# C64_Keyb-Test-ext.net
KiCad netlist of a schematic drawn in EAGLE
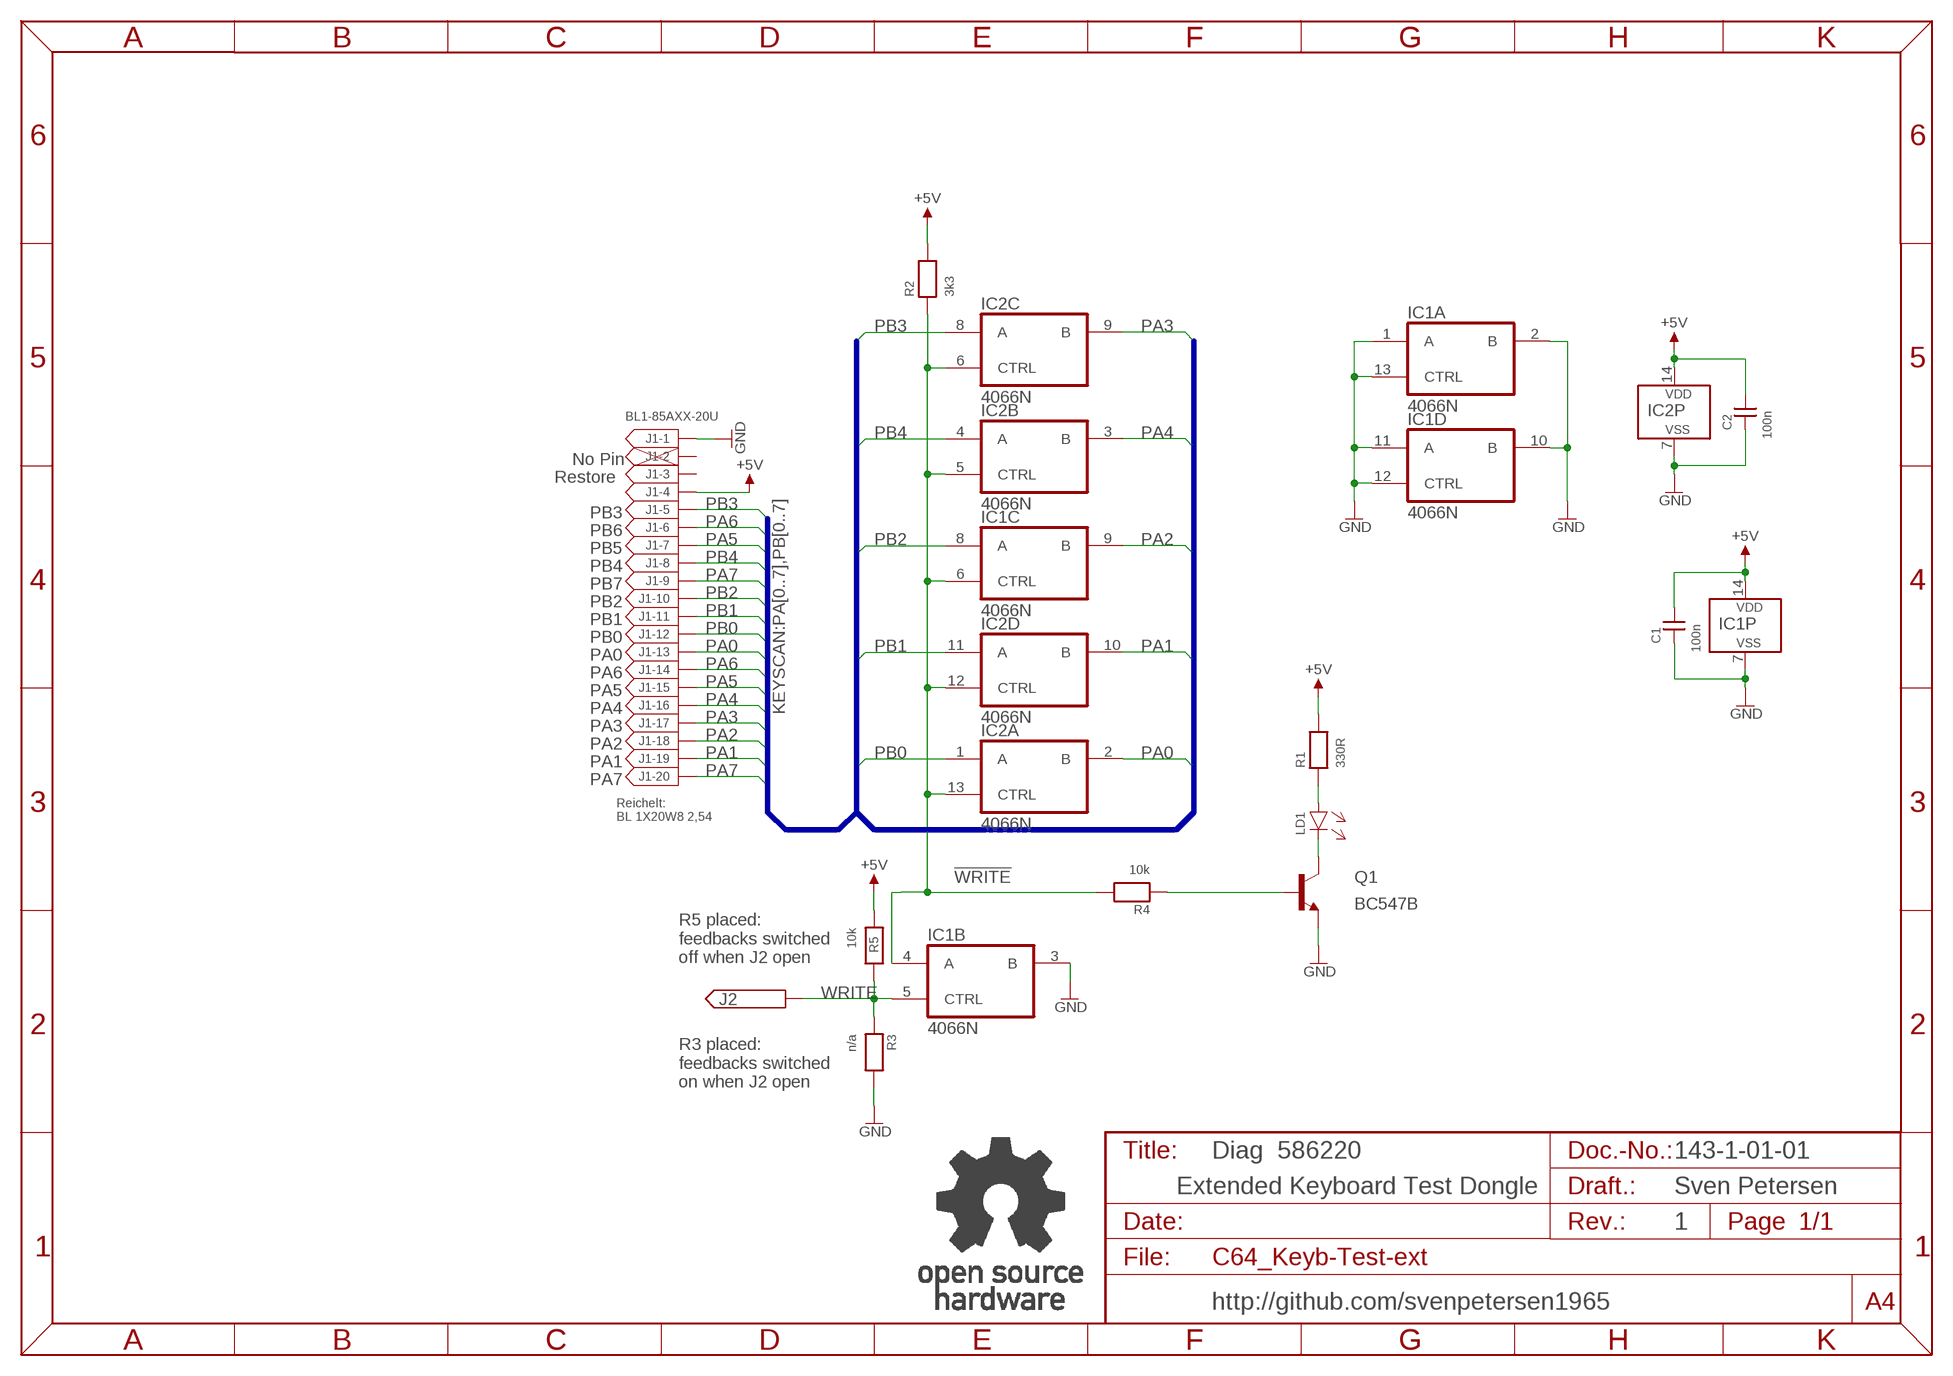
[diagram p0: schematic, sheet 1]

(export (version "E")
  (design (tool "Eeschema 10.0.6"))
  (components
    (comp (ref "C1")
      (value "100n")
      (footprint "eagle-import:C-2,5")
      (libsource (lib "eagle-import") (part "CAP01"))
    )
    (comp (ref "C2")
      (value "100n")
      (footprint "eagle-import:C-2,5")
      (libsource (lib "eagle-import") (part "CAP01"))
    )
    (comp (ref "IC1")
      (value "4066N")
      (footprint "eagle-import:DIL14")
      (libsource (lib "eagle-import") (part "4066N"))
    )
    (comp (ref "IC2")
      (value "4066N")
      (footprint "eagle-import:DIL14")
      (libsource (lib "eagle-import") (part "4066N"))
    )
    (comp (ref "J1")
      (value "BL1-85AXX-20U")
      (footprint "eagle-import:BL1-85AXX-20U")
      (libsource (lib "eagle-import") (part "BL1-85AXX-20U"))
    )
    (comp (ref "J2")
      (value "PINHD-1X1")
      (footprint "eagle-import:1X01")
      (libsource (lib "eagle-import") (part "PINHD-1X1"))
    )
    (comp (ref "LD1")
      (value "3MM")
      (footprint "eagle-import:3MM")
      (libsource (lib "eagle-import") (part "3MM"))
    )
    (comp (ref "Q1")
      (value "BC547B")
      (footprint "eagle-import:TO92")
      (libsource (lib "eagle-import") (part "BC547B"))
    )
    (comp (ref "R1")
      (value "330R")
      (footprint "eagle-import:R-10")
      (libsource (lib "eagle-import") (part "RES04"))
    )
    (comp (ref "R2")
      (value "3k3")
      (footprint "eagle-import:R-10")
      (libsource (lib "eagle-import") (part "RES04"))
    )
    (comp (ref "R3")
      (value "n/a")
      (footprint "eagle-import:R-10")
      (libsource (lib "eagle-import") (part "RES04"))
    )
    (comp (ref "R4")
      (value "10k")
      (footprint "eagle-import:R-10")
      (libsource (lib "eagle-import") (part "RES04"))
    )
    (comp (ref "R5")
      (value "10k")
      (footprint "eagle-import:R-10")
      (libsource (lib "eagle-import") (part "RES04"))
    )
    (comp (ref "U$19")
      (value "OPEN_SOURCE_HW")
      (footprint "eagle-import:OPENHW")
      (libsource (lib "eagle-import") (part "OPEN_SOURCE_HW"))
    )
  )
  (nets
    (net (code "1") (name "+5V") (class "Default")
      (node (ref "C1") (pin "2") (pinfunction "2_2") (pintype "passive"))
      (node (ref "C2") (pin "2") (pinfunction "2_2") (pintype "passive"))
      (node (ref "IC1") (pin "14") (pinfunction "VDD_14") (pintype "power_in"))
      (node (ref "IC2") (pin "14") (pinfunction "VDD_14") (pintype "power_in"))
      (node (ref "J1") (pin "4") (pinfunction "1_4") (pintype "bidirectional"))
      (node (ref "R1") (pin "2") (pinfunction "2_2") (pintype "passive"))
      (node (ref "R2") (pin "2") (pinfunction "2_2") (pintype "passive"))
      (node (ref "R5") (pin "1") (pinfunction "1_1") (pintype "passive"))
    )
    (net (code "2") (name "/PA0") (class "Default")
      (node (ref "IC2") (pin "2") (pinfunction "B_2") (pintype "tri_state"))
      (node (ref "J1") (pin "13") (pinfunction "1_13") (pintype "bidirectional"))
    )
    (net (code "3") (name "/PA1") (class "Default")
      (node (ref "IC2") (pin "10") (pinfunction "B_10") (pintype "tri_state"))
      (node (ref "J1") (pin "19") (pinfunction "1_19") (pintype "bidirectional"))
    )
    (net (code "4") (name "/PA2") (class "Default")
      (node (ref "IC1") (pin "9") (pinfunction "B_9") (pintype "tri_state"))
      (node (ref "J1") (pin "18") (pinfunction "1_18") (pintype "bidirectional"))
    )
    (net (code "5") (name "/PA3") (class "Default")
      (node (ref "IC2") (pin "9") (pinfunction "B_9") (pintype "tri_state"))
      (node (ref "J1") (pin "17") (pinfunction "1_17") (pintype "bidirectional"))
    )
    (net (code "6") (name "/PA4") (class "Default")
      (node (ref "IC2") (pin "3") (pinfunction "B_3") (pintype "tri_state"))
      (node (ref "J1") (pin "16") (pinfunction "1_16") (pintype "bidirectional"))
    )
    (net (code "7") (name "/PA5") (class "Default")
      (node (ref "J1") (pin "15") (pinfunction "1_15") (pintype "bidirectional"))
      (node (ref "J1") (pin "7") (pinfunction "1_7") (pintype "bidirectional"))
    )
    (net (code "8") (name "/PA6") (class "Default")
      (node (ref "J1") (pin "14") (pinfunction "1_14") (pintype "bidirectional"))
      (node (ref "J1") (pin "6") (pinfunction "1_6") (pintype "bidirectional"))
    )
    (net (code "9") (name "/PA7") (class "Default")
      (node (ref "J1") (pin "20") (pinfunction "1_20") (pintype "bidirectional"))
      (node (ref "J1") (pin "9") (pinfunction "1_9") (pintype "bidirectional"))
    )
    (net (code "10") (name "/PB0") (class "Default")
      (node (ref "IC2") (pin "1") (pinfunction "A_1") (pintype "tri_state"))
      (node (ref "J1") (pin "12") (pinfunction "1_12") (pintype "bidirectional"))
    )
    (net (code "11") (name "/PB1") (class "Default")
      (node (ref "IC2") (pin "11") (pinfunction "A_11") (pintype "tri_state"))
      (node (ref "J1") (pin "11") (pinfunction "1_11") (pintype "bidirectional"))
    )
    (net (code "12") (name "/PB2") (class "Default")
      (node (ref "IC1") (pin "8") (pinfunction "A_8") (pintype "tri_state"))
      (node (ref "J1") (pin "10") (pinfunction "1_10") (pintype "bidirectional"))
    )
    (net (code "13") (name "/PB3") (class "Default")
      (node (ref "IC2") (pin "8") (pinfunction "A_8") (pintype "tri_state"))
      (node (ref "J1") (pin "5") (pinfunction "1_5") (pintype "bidirectional"))
    )
    (net (code "14") (name "/PB4") (class "Default")
      (node (ref "IC2") (pin "4") (pinfunction "A_4") (pintype "tri_state"))
      (node (ref "J1") (pin "8") (pinfunction "1_8") (pintype "bidirectional"))
    )
    (net (code "15") (name "/WRITE") (class "Default")
      (node (ref "IC1") (pin "5") (pinfunction "CTRL_5") (pintype "input"))
      (node (ref "J2") (pin "1") (pinfunction "1_1") (pintype "passive"))
      (node (ref "R3") (pin "1") (pinfunction "1_1") (pintype "passive"))
      (node (ref "R5") (pin "2") (pinfunction "2_2") (pintype "passive"))
    )
    (net (code "17") (name "/~{WRITE}") (class "Default")
      (node (ref "IC1") (pin "4") (pinfunction "A_4") (pintype "tri_state"))
      (node (ref "IC1") (pin "6") (pinfunction "CTRL_6") (pintype "input"))
      (node (ref "IC2") (pin "12") (pinfunction "CTRL_12") (pintype "input"))
      (node (ref "IC2") (pin "13") (pinfunction "CTRL_13") (pintype "input"))
      (node (ref "IC2") (pin "5") (pinfunction "CTRL_5") (pintype "input"))
      (node (ref "IC2") (pin "6") (pinfunction "CTRL_6") (pintype "input"))
      (node (ref "R2") (pin "1") (pinfunction "1_1") (pintype "passive"))
      (node (ref "R4") (pin "2") (pinfunction "2_2") (pintype "passive"))
    )
    (net (code "18") (name "GND") (class "Default")
      (node (ref "C1") (pin "1") (pinfunction "1_1") (pintype "passive"))
      (node (ref "C2") (pin "1") (pinfunction "1_1") (pintype "passive"))
      (node (ref "IC1") (pin "1") (pinfunction "A_1") (pintype "tri_state"))
      (node (ref "IC1") (pin "10") (pinfunction "B_10") (pintype "tri_state"))
      (node (ref "IC1") (pin "11") (pinfunction "A_11") (pintype "tri_state"))
      (node (ref "IC1") (pin "12") (pinfunction "CTRL_12") (pintype "input"))
      (node (ref "IC1") (pin "13") (pinfunction "CTRL_13") (pintype "input"))
      (node (ref "IC1") (pin "2") (pinfunction "B_2") (pintype "tri_state"))
      (node (ref "IC1") (pin "3") (pinfunction "B_3") (pintype "tri_state"))
      (node (ref "IC1") (pin "7") (pinfunction "VSS_7") (pintype "power_in"))
      (node (ref "IC2") (pin "7") (pinfunction "VSS_7") (pintype "power_in"))
      (node (ref "J1") (pin "1") (pinfunction "1_1") (pintype "bidirectional"))
      (node (ref "Q1") (pin "1") (pinfunction "E_1") (pintype "passive"))
      (node (ref "R3") (pin "2") (pinfunction "2_2") (pintype "passive"))
    )
    (net (code "19") (name "Net-(LD1-K)") (class "Default")
      (node (ref "LD1") (pin "C") (pinfunction "K_C") (pintype "bidirectional"))
      (node (ref "Q1") (pin "3") (pinfunction "C_3") (pintype "passive"))
    )
    (net (code "20") (name "Net-(LD1-PadA)") (class "Default")
      (node (ref "LD1") (pin "A") (pinfunction "A_A") (pintype "bidirectional"))
      (node (ref "R1") (pin "1") (pinfunction "1_1") (pintype "passive"))
    )
    (net (code "21") (name "Net-(Q1-B)") (class "Default")
      (node (ref "Q1") (pin "2") (pinfunction "B_2") (pintype "passive"))
      (node (ref "R4") (pin "1") (pinfunction "1_1") (pintype "passive"))
    )
    (net (code "22") (name "unconnected-(J1L-1-Pad2)") (class "Default")
      (node (ref "J1") (pin "2") (pinfunction "1_2") (pintype "bidirectional"))
    )
    (net (code "23") (name "unconnected-(J1N-1-Pad3)") (class "Default")
      (node (ref "J1") (pin "3") (pinfunction "1_3") (pintype "bidirectional"))
    )
  )
)
